# ATmega128_V1_0.net
KiCad netlist of a schematic drawn in Altium Designer
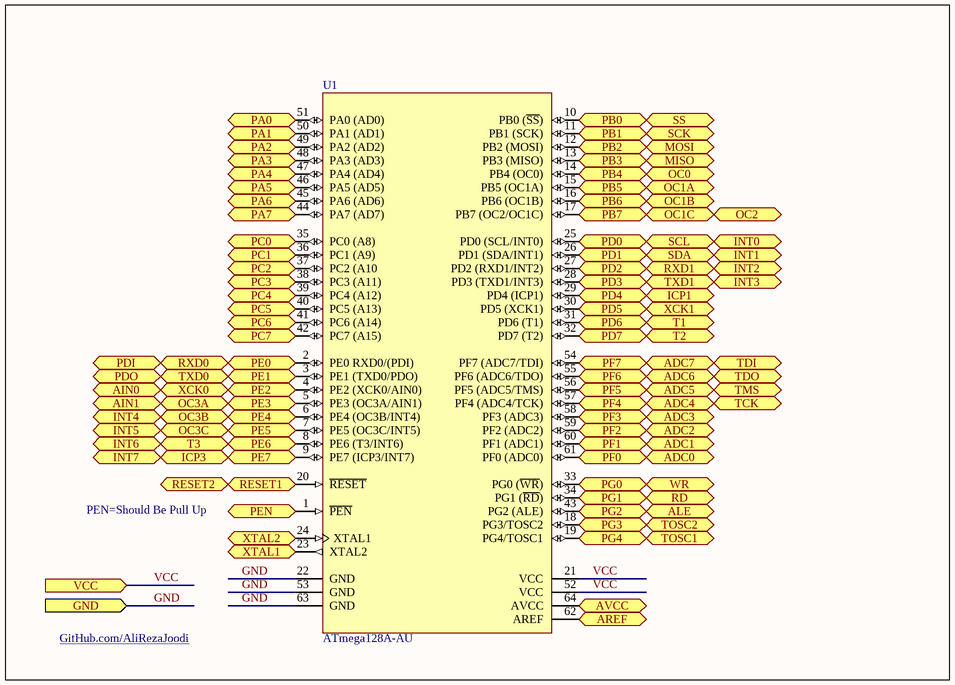
[diagram p0: ATmega128 V1.0.SchDoc]

(export (version "E")
  (design (tool "Eeschema 10.0.6"))
  (components
    (comp (ref "U1")
      (value "ATmega128A-AU")
      (footprint "64A_M")
      (fields (field (name "PUBLISHER") "Altium Limited"))
      (libsource (lib "Atmel Microcontroller 8-Bit megaAVR") (part "ATmega128A-AU"))
    )
  )
  (nets
    (net (code "14") (name "/AREF") (class "Default")
      (node (ref "U1") (pin "62") (pinfunction "AREF_62") (pintype "power_in"))
    )
    (net (code "35") (name "/AVCC") (class "Default")
      (node (ref "U1") (pin "64") (pinfunction "AVCC_64") (pintype "power_in"))
    )
    (net (code "36") (name "/GND") (class "Default")
      (node (ref "U1") (pin "22") (pinfunction "GND_22") (pintype "power_in"))
      (node (ref "U1") (pin "53") (pinfunction "GND_53") (pintype "power_in"))
      (node (ref "U1") (pin "63") (pinfunction "GND_63") (pintype "power_in"))
    )
    (net (code "37") (name "/PA0") (class "Default")
      (node (ref "U1") (pin "51") (pinfunction "PA0_(AD0)_51") (pintype "bidirectional"))
    )
    (net (code "38") (name "/PA1") (class "Default")
      (node (ref "U1") (pin "50") (pinfunction "PA1_(AD1)_50") (pintype "bidirectional"))
    )
    (net (code "39") (name "/PA2") (class "Default")
      (node (ref "U1") (pin "49") (pinfunction "PA2_(AD2)_49") (pintype "bidirectional"))
    )
    (net (code "40") (name "/PA3") (class "Default")
      (node (ref "U1") (pin "48") (pinfunction "PA3_(AD3)_48") (pintype "bidirectional"))
    )
    (net (code "41") (name "/PA4") (class "Default")
      (node (ref "U1") (pin "47") (pinfunction "PA4_(AD4)_47") (pintype "bidirectional"))
    )
    (net (code "42") (name "/PA5") (class "Default")
      (node (ref "U1") (pin "46") (pinfunction "PA5_(AD5)_46") (pintype "bidirectional"))
    )
    (net (code "51") (name "/PA6") (class "Default")
      (node (ref "U1") (pin "45") (pinfunction "PA6_(AD6)_45") (pintype "bidirectional"))
    )
    (net (code "52") (name "/PA7") (class "Default")
      (node (ref "U1") (pin "44") (pinfunction "PA7_(AD7)_44") (pintype "bidirectional"))
    )
    (net (code "53") (name "/PC0") (class "Default")
      (node (ref "U1") (pin "35") (pinfunction "PC0_(A8)_35") (pintype "bidirectional"))
    )
    (net (code "54") (name "/PC1") (class "Default")
      (node (ref "U1") (pin "36") (pinfunction "PC1_(A9)_36") (pintype "bidirectional"))
    )
    (net (code "55") (name "/PC2") (class "Default")
      (node (ref "U1") (pin "37") (pinfunction "PC2_(A10_37") (pintype "bidirectional"))
    )
    (net (code "56") (name "/PC3") (class "Default")
      (node (ref "U1") (pin "38") (pinfunction "PC3_(A11)_38") (pintype "bidirectional"))
    )
    (net (code "57") (name "/PC4") (class "Default")
      (node (ref "U1") (pin "39") (pinfunction "PC4_(A12)_39") (pintype "bidirectional"))
    )
    (net (code "58") (name "/PC5") (class "Default")
      (node (ref "U1") (pin "40") (pinfunction "PC5_(A13)_40") (pintype "bidirectional"))
    )
    (net (code "69") (name "/PC6") (class "Default")
      (node (ref "U1") (pin "41") (pinfunction "PC6_(A14)_41") (pintype "bidirectional"))
    )
    (net (code "70") (name "/PC7") (class "Default")
      (node (ref "U1") (pin "42") (pinfunction "PC7_(A15)_42") (pintype "bidirectional"))
    )
    (net (code "71") (name "/PE0") (class "Default")
      (node (ref "U1") (pin "2") (pinfunction "PE0_RXD0/(PDI)_2") (pintype "bidirectional"))
    )
    (net (code "72") (name "/PE1") (class "Default")
      (node (ref "U1") (pin "3") (pinfunction "PE1_(TXD0/PDO)_3") (pintype "bidirectional"))
    )
    (net (code "73") (name "/PE2") (class "Default")
      (node (ref "U1") (pin "4") (pinfunction "PE2_(XCK0/AIN0)_4") (pintype "bidirectional"))
    )
    (net (code "74") (name "/PE3") (class "Default")
      (node (ref "U1") (pin "5") (pinfunction "PE3_(OC3A/AIN1)_5") (pintype "bidirectional"))
    )
    (net (code "75") (name "/PE4") (class "Default")
      (node (ref "U1") (pin "6") (pinfunction "PE4_(OC3B/INT4)_6") (pintype "bidirectional"))
    )
    (net (code "76") (name "/PE5") (class "Default")
      (node (ref "U1") (pin "7") (pinfunction "PE5_(OC3C/INT5)_7") (pintype "bidirectional"))
    )
    (net (code "77") (name "/PE6") (class "Default")
      (node (ref "U1") (pin "8") (pinfunction "PE6_(T3/INT6)_8") (pintype "bidirectional"))
    )
    (net (code "92") (name "/PE7") (class "Default")
      (node (ref "U1") (pin "9") (pinfunction "PE7_(ICP3/INT7)_9") (pintype "bidirectional"))
    )
    (net (code "111") (name "/PEN") (class "Default")
      (node (ref "U1") (pin "1") (pinfunction "~{PEN}_1") (pintype "input"))
    )
    (net (code "115") (name "/RESET1") (class "Default")
      (node (ref "U1") (pin "20") (pinfunction "~{RESET}_20") (pintype "input"))
    )
    (net (code "116") (name "/VCC") (class "Default")
      (node (ref "U1") (pin "21") (pinfunction "VCC_21") (pintype "power_in"))
      (node (ref "U1") (pin "52") (pinfunction "VCC_52") (pintype "power_in"))
    )
    (net (code "117") (name "/XTAL1") (class "Default")
      (node (ref "U1") (pin "23") (pinfunction "XTAL2_23") (pintype "output"))
    )
    (net (code "118") (name "/XTAL2") (class "Default")
      (node (ref "U1") (pin "24") (pinfunction "XTAL1_24") (pintype "input"))
    )
    (net (code "119") (name "unconnected-(U1-PB0_(~{SS})-Pad10)") (class "Default")
      (node (ref "U1") (pin "10") (pinfunction "PB0_(~{SS})_10") (pintype "bidirectional"))
    )
    (net (code "120") (name "unconnected-(U1-PB1_(SCK)-Pad11)") (class "Default")
      (node (ref "U1") (pin "11") (pinfunction "PB1_(SCK)_11") (pintype "bidirectional"))
    )
    (net (code "121") (name "unconnected-(U1-PB2_(MOSI)-Pad12)") (class "Default")
      (node (ref "U1") (pin "12") (pinfunction "PB2_(MOSI)_12") (pintype "bidirectional"))
    )
    (net (code "122") (name "unconnected-(U1-PB3_(MISO)-Pad13)") (class "Default")
      (node (ref "U1") (pin "13") (pinfunction "PB3_(MISO)_13") (pintype "bidirectional"))
    )
    (net (code "123") (name "unconnected-(U1-PB4_(OC0)-Pad14)") (class "Default")
      (node (ref "U1") (pin "14") (pinfunction "PB4_(OC0)_14") (pintype "bidirectional"))
    )
    (net (code "124") (name "unconnected-(U1-PB5_(OC1A)-Pad15)") (class "Default")
      (node (ref "U1") (pin "15") (pinfunction "PB5_(OC1A)_15") (pintype "bidirectional"))
    )
    (net (code "125") (name "unconnected-(U1-PB6_(OC1B)-Pad16)") (class "Default")
      (node (ref "U1") (pin "16") (pinfunction "PB6_(OC1B)_16") (pintype "bidirectional"))
    )
    (net (code "126") (name "unconnected-(U1-PB7_(OC2{slash}OC1C)-Pad17)") (class "Default")
      (node (ref "U1") (pin "17") (pinfunction "PB7_(OC2/OC1C)_17") (pintype "bidirectional"))
    )
    (net (code "127") (name "unconnected-(U1-PD0_(SCL{slash}INT0)-Pad25)") (class "Default")
      (node (ref "U1") (pin "25") (pinfunction "PD0_(SCL/INT0)_25") (pintype "bidirectional"))
    )
    (net (code "128") (name "unconnected-(U1-PD1_(SDA{slash}INT1)-Pad26)") (class "Default")
      (node (ref "U1") (pin "26") (pinfunction "PD1_(SDA/INT1)_26") (pintype "bidirectional"))
    )
    (net (code "129") (name "unconnected-(U1-PD2_(RXD1{slash}INT2)-Pad27)") (class "Default")
      (node (ref "U1") (pin "27") (pinfunction "PD2_(RXD1/INT2)_27") (pintype "bidirectional"))
    )
    (net (code "130") (name "unconnected-(U1-PD3_(TXD1{slash}INT3)-Pad28)") (class "Default")
      (node (ref "U1") (pin "28") (pinfunction "PD3_(TXD1/INT3)_28") (pintype "bidirectional"))
    )
    (net (code "131") (name "unconnected-(U1-PD4_(ICP1)-Pad29)") (class "Default")
      (node (ref "U1") (pin "29") (pinfunction "PD4_(ICP1)_29") (pintype "bidirectional"))
    )
    (net (code "132") (name "unconnected-(U1-PD5_(XCK1)-Pad30)") (class "Default")
      (node (ref "U1") (pin "30") (pinfunction "PD5_(XCK1)_30") (pintype "bidirectional"))
    )
    (net (code "133") (name "unconnected-(U1-PD6_(T1)-Pad31)") (class "Default")
      (node (ref "U1") (pin "31") (pinfunction "PD6_(T1)_31") (pintype "bidirectional"))
    )
    (net (code "134") (name "unconnected-(U1-PD7_(T2)-Pad32)") (class "Default")
      (node (ref "U1") (pin "32") (pinfunction "PD7_(T2)_32") (pintype "bidirectional"))
    )
    (net (code "135") (name "unconnected-(U1-PF0_(ADC0)-Pad61)") (class "Default")
      (node (ref "U1") (pin "61") (pinfunction "PF0_(ADC0)_61") (pintype "bidirectional"))
    )
    (net (code "136") (name "unconnected-(U1-PF1_(ADC1)-Pad60)") (class "Default")
      (node (ref "U1") (pin "60") (pinfunction "PF1_(ADC1)_60") (pintype "bidirectional"))
    )
    (net (code "137") (name "unconnected-(U1-PF2_(ADC2)-Pad59)") (class "Default")
      (node (ref "U1") (pin "59") (pinfunction "PF2_(ADC2)_59") (pintype "bidirectional"))
    )
    (net (code "138") (name "unconnected-(U1-PF3_(ADC3)-Pad58)") (class "Default")
      (node (ref "U1") (pin "58") (pinfunction "PF3_(ADC3)_58") (pintype "bidirectional"))
    )
    (net (code "139") (name "unconnected-(U1-PF4_(ADC4{slash}TCK)-Pad57)") (class "Default")
      (node (ref "U1") (pin "57") (pinfunction "PF4_(ADC4/TCK)_57") (pintype "bidirectional"))
    )
    (net (code "140") (name "unconnected-(U1-PF5_(ADC5{slash}TMS)-Pad56)") (class "Default")
      (node (ref "U1") (pin "56") (pinfunction "PF5_(ADC5/TMS)_56") (pintype "bidirectional"))
    )
    (net (code "141") (name "unconnected-(U1-PF6_(ADC6{slash}TDO)-Pad55)") (class "Default")
      (node (ref "U1") (pin "55") (pinfunction "PF6_(ADC6/TDO)_55") (pintype "bidirectional"))
    )
    (net (code "142") (name "unconnected-(U1-PF7_(ADC7{slash}TDI)-Pad54)") (class "Default")
      (node (ref "U1") (pin "54") (pinfunction "PF7_(ADC7/TDI)_54") (pintype "bidirectional"))
    )
    (net (code "143") (name "unconnected-(U1-PG0_(~{WR})-Pad33)") (class "Default")
      (node (ref "U1") (pin "33") (pinfunction "PG0_(~{WR})_33") (pintype "bidirectional"))
    )
    (net (code "144") (name "unconnected-(U1-PG1_(~{RD})-Pad34)") (class "Default")
      (node (ref "U1") (pin "34") (pinfunction "PG1_(~{RD})_34") (pintype "bidirectional"))
    )
    (net (code "145") (name "unconnected-(U1-PG2_(ALE)-Pad43)") (class "Default")
      (node (ref "U1") (pin "43") (pinfunction "PG2_(ALE)_43") (pintype "bidirectional"))
    )
    (net (code "146") (name "unconnected-(U1-PG3{slash}TOSC2-Pad18)") (class "Default")
      (node (ref "U1") (pin "18") (pinfunction "PG3/TOSC2_18") (pintype "bidirectional"))
    )
    (net (code "147") (name "unconnected-(U1-PG4{slash}TOSC1-Pad19)") (class "Default")
      (node (ref "U1") (pin "19") (pinfunction "PG4/TOSC1_19") (pintype "bidirectional"))
    )
  )
)
